# Encoders.net
KiCad netlist of a schematic drawn in Altium Designer
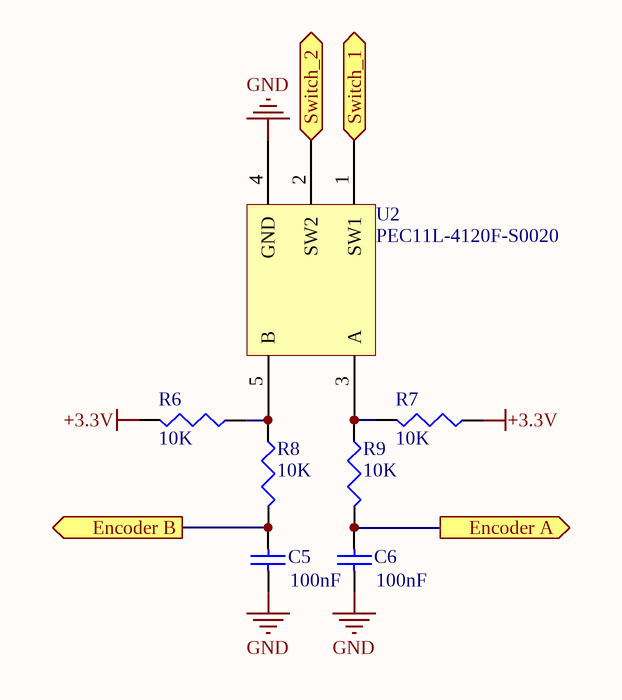
[diagram p0: Encoders.SchDoc]

(export (version "E")
  (design (tool "Eeschema 10.0.6"))
  (components
    (comp (ref "C5")
      (value "100nF")
      (footprint "RES_0603")
      (description "Capacitor")
      (fields
        (field (name "MANUFACTURER") "AVX Corporation")
        (field (name "MANUFACTURER PART NUMBER") "06035G104ZAT2A")
      )
      (libsource (lib "Miscellaneous Devices") (part "Cap"))
    )
    (comp (ref "C6")
      (value "100nF")
      (footprint "RES_0603")
      (description "Capacitor")
      (fields
        (field (name "MANUFACTURER") "AVX Corporation")
        (field (name "MANUFACTURER PART NUMBER") "06035G104ZAT2A")
      )
      (libsource (lib "Miscellaneous Devices") (part "Cap"))
    )
    (comp (ref "R6")
      (value "10K")
      (footprint "RES_0805")
      (description "Resistor")
      (fields
        (field (name "MANUFACTURER") "Susumu")
        (field (name "MANUFACTURER PART NUMBER") "RR1220P-103-D")
      )
      (libsource (lib "Miscellaneous Devices") (part "Res3"))
    )
    (comp (ref "R7")
      (value "10K")
      (footprint "RES_0805")
      (description "Resistor")
      (fields
        (field (name "MANUFACTURER") "Susumu")
        (field (name "MANUFACTURER PART NUMBER") "RR1220P-103-D")
      )
      (libsource (lib "Miscellaneous Devices") (part "Res3"))
    )
    (comp (ref "R8")
      (value "10K")
      (footprint "RES_0805")
      (description "Resistor")
      (fields
        (field (name "MANUFACTURER") "Susumu")
        (field (name "MANUFACTURER PART NUMBER") "RR1220P-103-D")
      )
      (libsource (lib "Miscellaneous Devices") (part "Res3"))
    )
    (comp (ref "R9")
      (value "10K")
      (footprint "RES_0805")
      (description "Resistor")
      (fields
        (field (name "MANUFACTURER") "Susumu")
        (field (name "MANUFACTURER PART NUMBER") "RR1220P-103-D")
      )
      (libsource (lib "Miscellaneous Devices") (part "Res3"))
    )
    (comp (ref "U2")
      (value "PEC11L-4120F-S0020")
      (footprint "ENC5")
      (description "Rotary Encoder with Switch")
      (fields (field (name "MANUFACTURER") "Bourns Inc."))
      (libsource (lib "Custom") (part "PEC11-4215F-S24"))
    )
  )
  (nets
    (net (code "1") (name "+3.3V") (class "Default")
      (node (ref "R6") (pin "2") (pinfunction "2_2") (pintype "passive"))
      (node (ref "R7") (pin "1") (pinfunction "1_1") (pintype "passive"))
    )
    (net (code "2") (name "/Encoder A") (class "Default")
      (node (ref "C6") (pin "2") (pinfunction "2_2") (pintype "passive"))
      (node (ref "R9") (pin "2") (pinfunction "2_2") (pintype "passive"))
    )
    (net (code "3") (name "/Encoder B") (class "Default")
      (node (ref "C5") (pin "2") (pinfunction "2_2") (pintype "passive"))
      (node (ref "R8") (pin "2") (pinfunction "2_2") (pintype "passive"))
    )
    (net (code "4") (name "/Switch_1") (class "Default")
      (node (ref "U2") (pin "1") (pinfunction "SW1_1") (pintype "passive"))
    )
    (net (code "5") (name "/Switch_2") (class "Default")
      (node (ref "U2") (pin "2") (pinfunction "SW2_2") (pintype "passive"))
    )
    (net (code "6") (name "GND") (class "Default")
      (node (ref "C5") (pin "1") (pinfunction "1_1") (pintype "passive"))
      (node (ref "C6") (pin "1") (pinfunction "1_1") (pintype "passive"))
      (node (ref "U2") (pin "4") (pinfunction "GND_4") (pintype "passive"))
    )
    (net (code "7") (name "Net-(U2-A)") (class "Default")
      (node (ref "R7") (pin "2") (pinfunction "2_2") (pintype "passive"))
      (node (ref "R9") (pin "1") (pinfunction "1_1") (pintype "passive"))
      (node (ref "U2") (pin "3") (pinfunction "A_3") (pintype "passive"))
    )
    (net (code "8") (name "Net-(U2-B)") (class "Default")
      (node (ref "R6") (pin "1") (pinfunction "1_1") (pintype "passive"))
      (node (ref "R8") (pin "1") (pinfunction "1_1") (pintype "passive"))
      (node (ref "U2") (pin "5") (pinfunction "B_5") (pintype "passive"))
    )
  )
)
